# workInProgTCIAADC.net
KiCad netlist of a schematic drawn in EAGLE
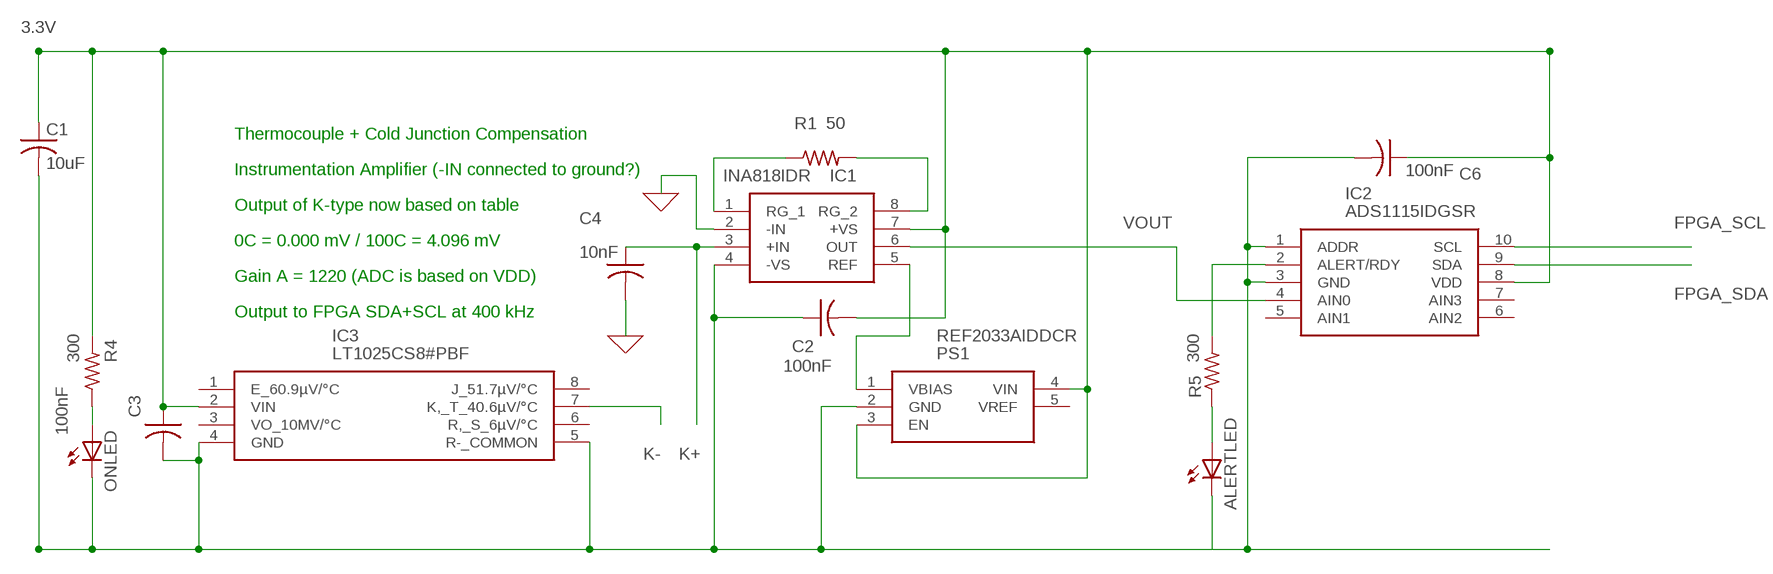
[diagram p0: schematic, sheet 1]

(export (version "E")
  (design (tool "Eeschema 10.0.6"))
  (components
    (comp (ref "ALERTLED")
      (value "LEDCHIP-LED0805")
      (footprint "eagle-import:CHIP-LED0805")
      (libsource (lib "eagle-import") (part "LEDCHIP-LED0805"))
    )
    (comp (ref "C1")
      (value "10uF")
      (footprint "eagle-import:C0805")
      (libsource (lib "eagle-import") (part "C-USC0805"))
    )
    (comp (ref "C2")
      (value "100nF")
      (footprint "eagle-import:C0805")
      (libsource (lib "eagle-import") (part "C-USC0805"))
    )
    (comp (ref "C3")
      (value "100nF")
      (footprint "eagle-import:C0805")
      (libsource (lib "eagle-import") (part "C-USC0805"))
    )
    (comp (ref "C4")
      (value "10nF")
      (footprint "eagle-import:C0805")
      (libsource (lib "eagle-import") (part "C-USC0805"))
    )
    (comp (ref "C6")
      (value "100nF")
      (footprint "eagle-import:C0805")
      (libsource (lib "eagle-import") (part "C-USC0805"))
    )
    (comp (ref "IC1")
      (value "INA818IDR")
      (footprint "eagle-import:SOIC127P600X175-8N")
      (fields (field (name "MOUSER_PART_NUMBER") "595-INA818IDR"))
      (libsource (lib "eagle-import") (part "INA818IDR"))
    )
    (comp (ref "IC2")
      (value "ADS1115IDGSR")
      (footprint "eagle-import:SOP50P490X110-10N")
      (fields (field (name "MOUSER_PART_NUMBER") "595-ADS1115IDGSR"))
      (libsource (lib "eagle-import") (part "ADS1115IDGSR"))
    )
    (comp (ref "IC3")
      (value "LT1025CS8#PBF")
      (footprint "eagle-import:SOIC127P599X175-8N")
      (fields (field (name "MOUSER_PART_NUMBER") "584-LT1025CS8#PBF"))
      (libsource (lib "eagle-import") (part "LT1025CS8#PBF"))
    )
    (comp (ref "ONLED")
      (value "LEDCHIP-LED0805")
      (footprint "eagle-import:CHIP-LED0805")
      (libsource (lib "eagle-import") (part "LEDCHIP-LED0805"))
    )
    (comp (ref "PS1")
      (value "REF2033AIDDCR")
      (footprint "eagle-import:SOT95P280X110-5N")
      (fields (field (name "MOUSER_PART_NUMBER") "595-REF2033AIDDCR"))
      (libsource (lib "eagle-import") (part "REF2033AIDDCR"))
    )
    (comp (ref "R1")
      (value "50")
      (footprint "eagle-import:R0805")
      (libsource (lib "eagle-import") (part "R-US_R0805"))
    )
    (comp (ref "R4")
      (value "300")
      (footprint "eagle-import:R0805")
      (libsource (lib "eagle-import") (part "R-US_R0805"))
    )
    (comp (ref "R5")
      (value "300")
      (footprint "eagle-import:R0805")
      (libsource (lib "eagle-import") (part "R-US_R0805"))
    )
  )
  (nets
    (net (code "1") (name "/3.3V") (class "Default")
      (node (ref "C1") (pin "1") (pinfunction "1_1") (pintype "passive"))
      (node (ref "C2") (pin "2") (pinfunction "2_2") (pintype "passive"))
      (node (ref "C3") (pin "1") (pinfunction "1_1") (pintype "passive"))
      (node (ref "C6") (pin "1") (pinfunction "1_1") (pintype "passive"))
      (node (ref "IC1") (pin "7") (pinfunction "+VS_7") (pintype "bidirectional"))
      (node (ref "IC2") (pin "8") (pinfunction "VDD_8") (pintype "bidirectional"))
      (node (ref "IC3") (pin "2") (pinfunction "VIN_2") (pintype "bidirectional"))
      (node (ref "PS1") (pin "3") (pinfunction "EN_3") (pintype "bidirectional"))
      (node (ref "PS1") (pin "4") (pinfunction "VIN_4") (pintype "power_in"))
      (node (ref "R4") (pin "2") (pinfunction "2_2") (pintype "passive"))
    )
    (net (code "2") (name "/FPGA_SCL") (class "Default")
      (node (ref "IC2") (pin "10") (pinfunction "SCL_10") (pintype "bidirectional"))
    )
    (net (code "3") (name "/FPGA_SDA") (class "Default")
      (node (ref "IC2") (pin "9") (pinfunction "SDA_9") (pintype "bidirectional"))
    )
    (net (code "4") (name "/K+") (class "Default")
      (node (ref "C4") (pin "1") (pinfunction "1_1") (pintype "passive"))
      (node (ref "IC1") (pin "3") (pinfunction "+IN_3") (pintype "bidirectional"))
    )
    (net (code "5") (name "/K-") (class "Default")
      (node (ref "IC3") (pin "7") (pinfunction "K,_T_40.6µV/°C_7") (pintype "bidirectional"))
    )
    (net (code "6") (name "/VOUT") (class "Default")
      (node (ref "IC1") (pin "6") (pinfunction "OUT_6") (pintype "bidirectional"))
      (node (ref "IC2") (pin "4") (pinfunction "AIN0_4") (pintype "bidirectional"))
    )
    (net (code "7") (name "GND") (class "Default")
      (node (ref "C4") (pin "2") (pinfunction "2_2") (pintype "passive"))
      (node (ref "IC1") (pin "2") (pinfunction "-IN_2") (pintype "bidirectional"))
    )
    (net (code "8") (name "Net-(ALERTLED-PadA)") (class "Default")
      (node (ref "ALERTLED") (pin "A") (pinfunction "A_A") (pintype "passive"))
      (node (ref "R5") (pin "1") (pinfunction "1_1") (pintype "passive"))
    )
    (net (code "9") (name "Net-(IC1--VS)") (class "Default")
      (node (ref "C1") (pin "2") (pinfunction "2_2") (pintype "passive"))
      (node (ref "C2") (pin "1") (pinfunction "1_1") (pintype "passive"))
      (node (ref "C3") (pin "2") (pinfunction "2_2") (pintype "passive"))
      (node (ref "C6") (pin "2") (pinfunction "2_2") (pintype "passive"))
      (node (ref "IC1") (pin "4") (pinfunction "-VS_4") (pintype "bidirectional"))
      (node (ref "IC2") (pin "1") (pinfunction "ADDR_1") (pintype "bidirectional"))
      (node (ref "IC2") (pin "3") (pinfunction "GND_3") (pintype "bidirectional"))
      (node (ref "IC3") (pin "4") (pinfunction "GND_4") (pintype "bidirectional"))
      (node (ref "IC3") (pin "5") (pinfunction "R-_COMMON_5") (pintype "bidirectional"))
      (node (ref "ONLED") (pin "C") (pinfunction "C_C") (pintype "passive"))
      (node (ref "PS1") (pin "2") (pinfunction "GND_2") (pintype "power_in"))
    )
    (net (code "10") (name "Net-(IC1-REF)") (class "Default")
      (node (ref "IC1") (pin "5") (pinfunction "REF_5") (pintype "bidirectional"))
      (node (ref "PS1") (pin "1") (pinfunction "VBIAS_1") (pintype "output"))
    )
    (net (code "11") (name "Net-(IC1-RG_1)") (class "Default")
      (node (ref "IC1") (pin "1") (pinfunction "RG_1_1") (pintype "bidirectional"))
      (node (ref "R1") (pin "1") (pinfunction "1_1") (pintype "passive"))
    )
    (net (code "12") (name "Net-(IC1-RG_2)") (class "Default")
      (node (ref "IC1") (pin "8") (pinfunction "RG_2_8") (pintype "bidirectional"))
      (node (ref "R1") (pin "2") (pinfunction "2_2") (pintype "passive"))
    )
    (net (code "13") (name "Net-(IC2-ALERT{slash}RDY)") (class "Default")
      (node (ref "IC2") (pin "2") (pinfunction "ALERT/RDY_2") (pintype "bidirectional"))
      (node (ref "R5") (pin "2") (pinfunction "2_2") (pintype "passive"))
    )
    (net (code "14") (name "Net-(ONLED-PadA)") (class "Default")
      (node (ref "ONLED") (pin "A") (pinfunction "A_A") (pintype "passive"))
      (node (ref "R4") (pin "1") (pinfunction "1_1") (pintype "passive"))
    )
    (net (code "15") (name "unconnected-(ALERTLED-PadC)") (class "Default")
      (node (ref "ALERTLED") (pin "C") (pinfunction "C_C") (pintype "passive"))
    )
    (net (code "16") (name "unconnected-(IC2-AIN1-Pad5)") (class "Default")
      (node (ref "IC2") (pin "5") (pinfunction "AIN1_5") (pintype "bidirectional"))
    )
    (net (code "17") (name "unconnected-(IC2-AIN2-Pad6)") (class "Default")
      (node (ref "IC2") (pin "6") (pinfunction "AIN2_6") (pintype "bidirectional"))
    )
    (net (code "18") (name "unconnected-(IC2-AIN3-Pad7)") (class "Default")
      (node (ref "IC2") (pin "7") (pinfunction "AIN3_7") (pintype "bidirectional"))
    )
    (net (code "19") (name "unconnected-(IC3-E_60.9µV{slash}°C-Pad1)") (class "Default")
      (node (ref "IC3") (pin "1") (pinfunction "E_60.9µV/°C_1") (pintype "bidirectional"))
    )
    (net (code "20") (name "unconnected-(IC3-J_51.7µV{slash}°C-Pad8)") (class "Default")
      (node (ref "IC3") (pin "8") (pinfunction "J_51.7µV/°C_8") (pintype "bidirectional"))
    )
    (net (code "21") (name "unconnected-(IC3-R,_S_6µV{slash}°C-Pad6)") (class "Default")
      (node (ref "IC3") (pin "6") (pinfunction "R,_S_6µV/°C_6") (pintype "bidirectional"))
    )
    (net (code "22") (name "unconnected-(IC3-VO_10MV{slash}°C-Pad3)") (class "Default")
      (node (ref "IC3") (pin "3") (pinfunction "VO_10MV/°C_3") (pintype "bidirectional"))
    )
    (net (code "23") (name "unconnected-(PS1-VREF-Pad5)") (class "Default")
      (node (ref "PS1") (pin "5") (pinfunction "VREF_5") (pintype "output"))
    )
  )
)
